# 10-10.net
KiCad netlist of a schematic drawn in EasyEDA Pro
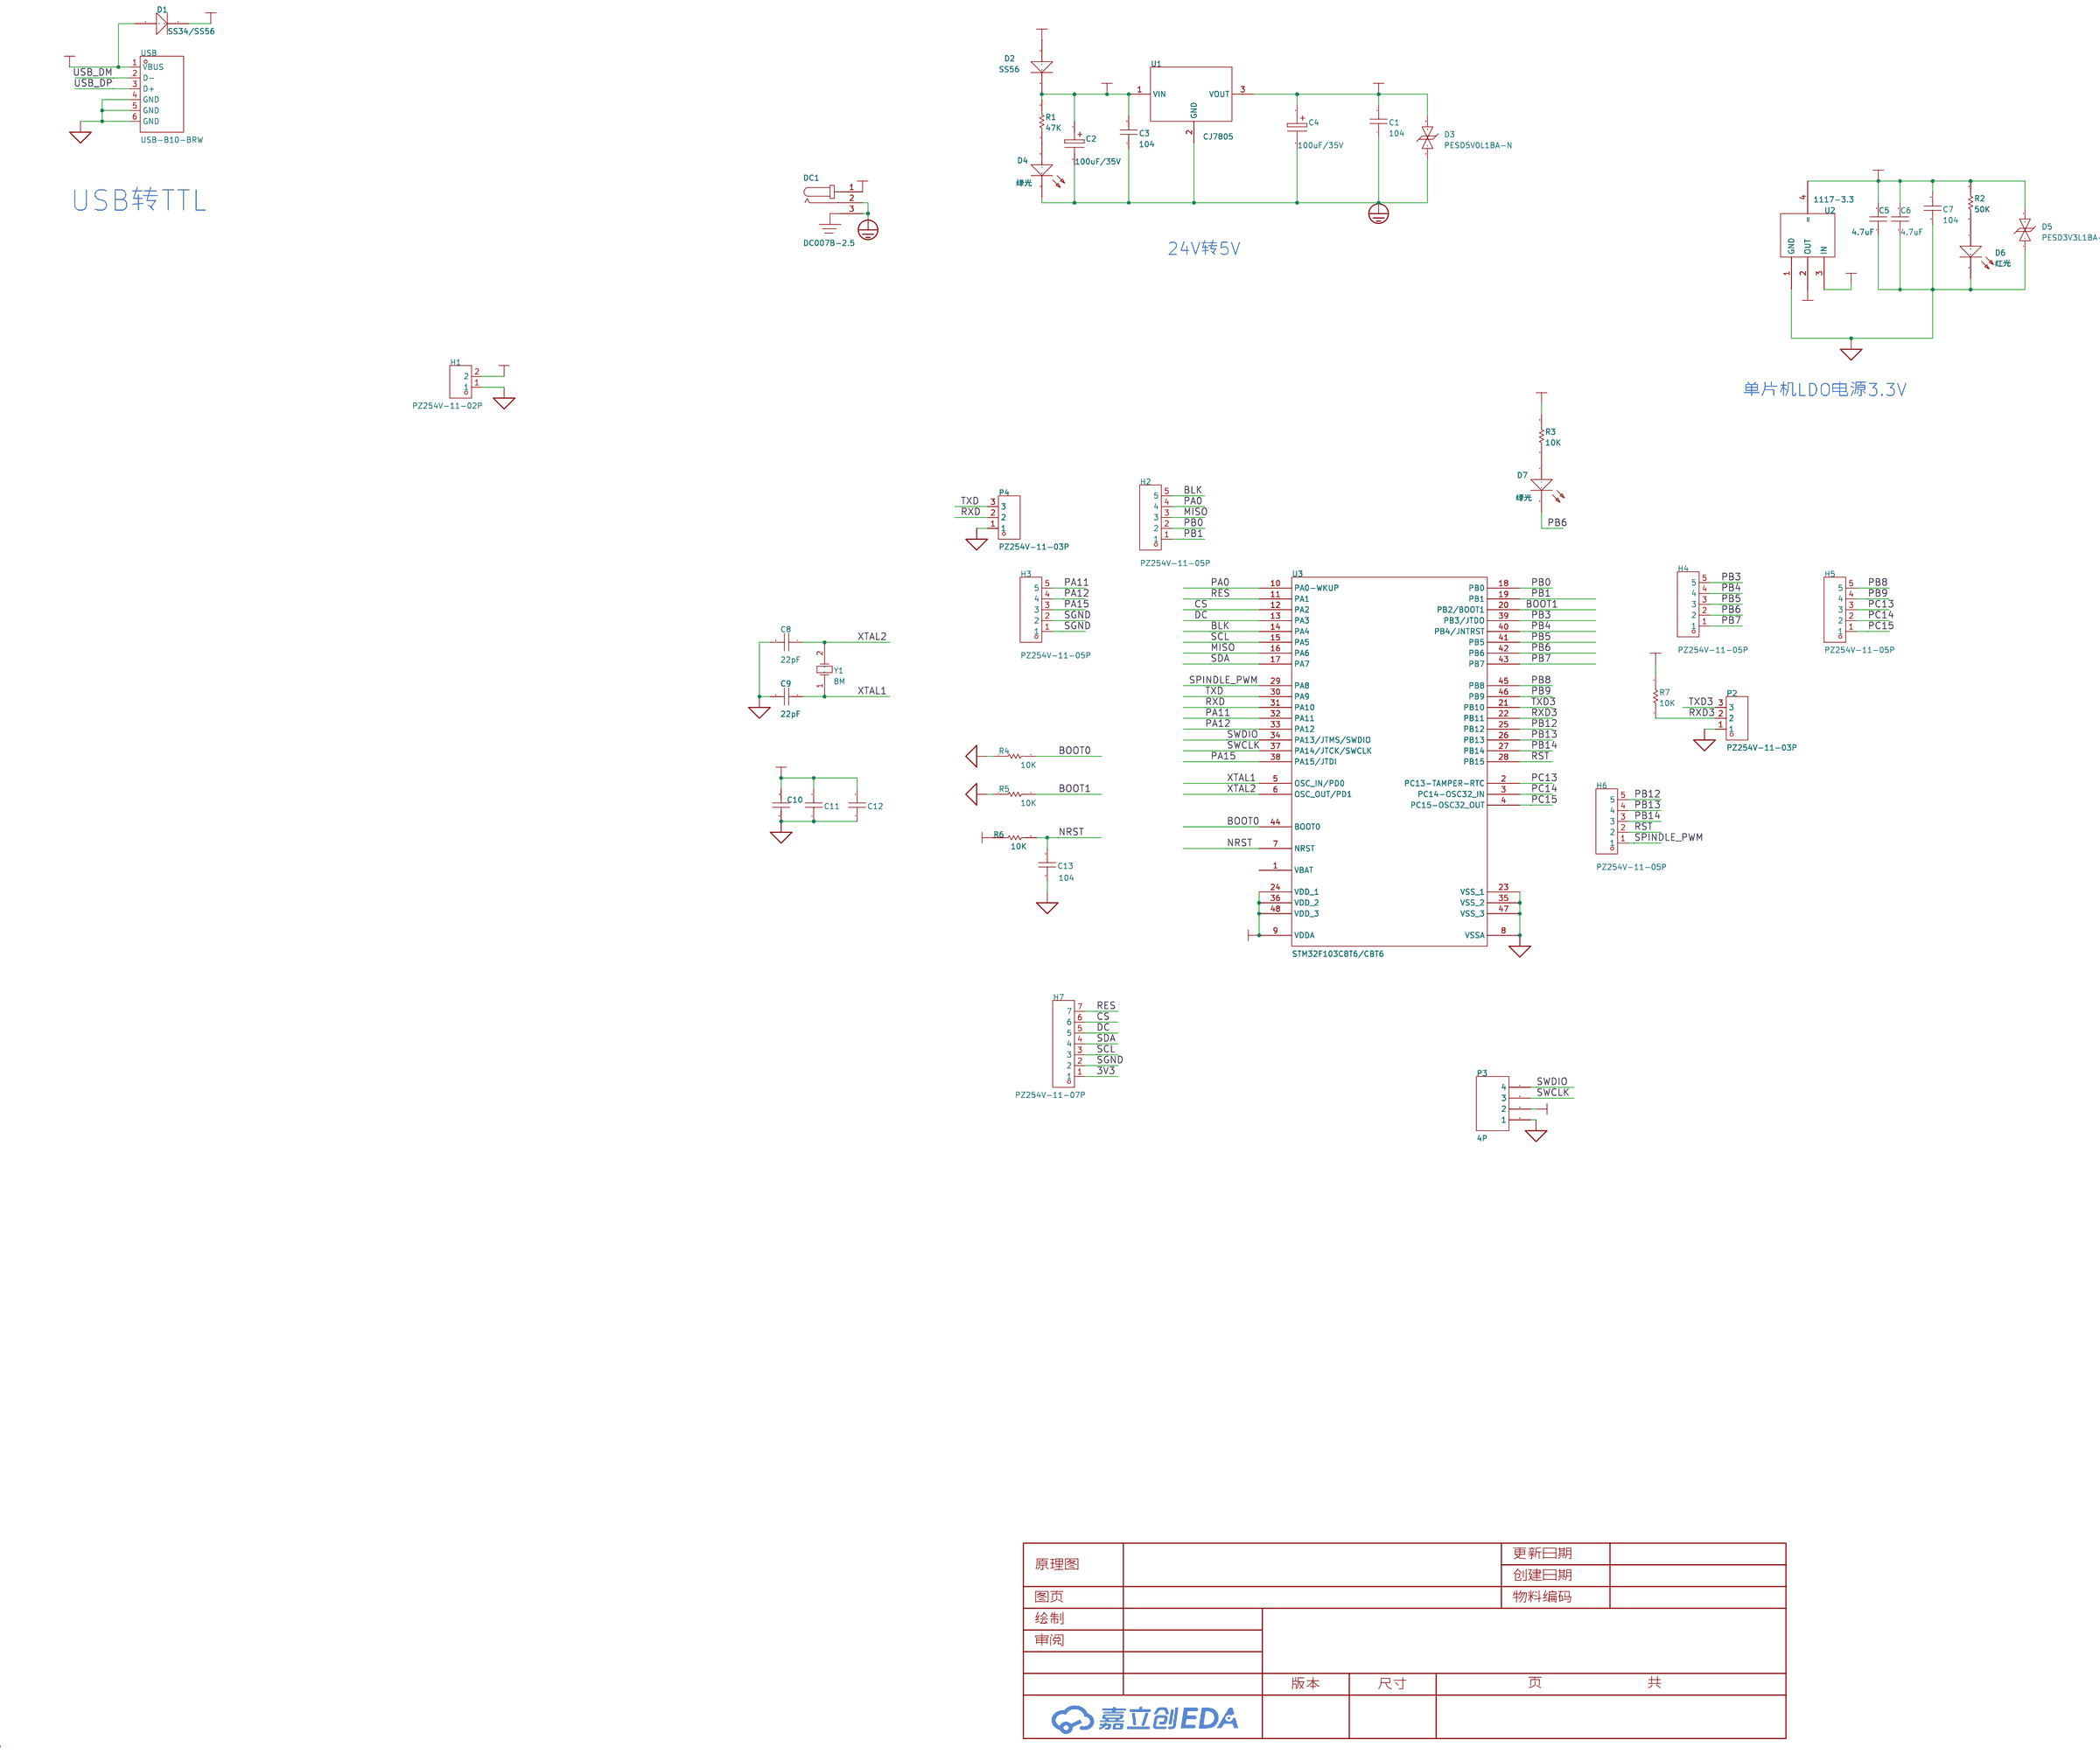
[diagram p0: 主控MCU]
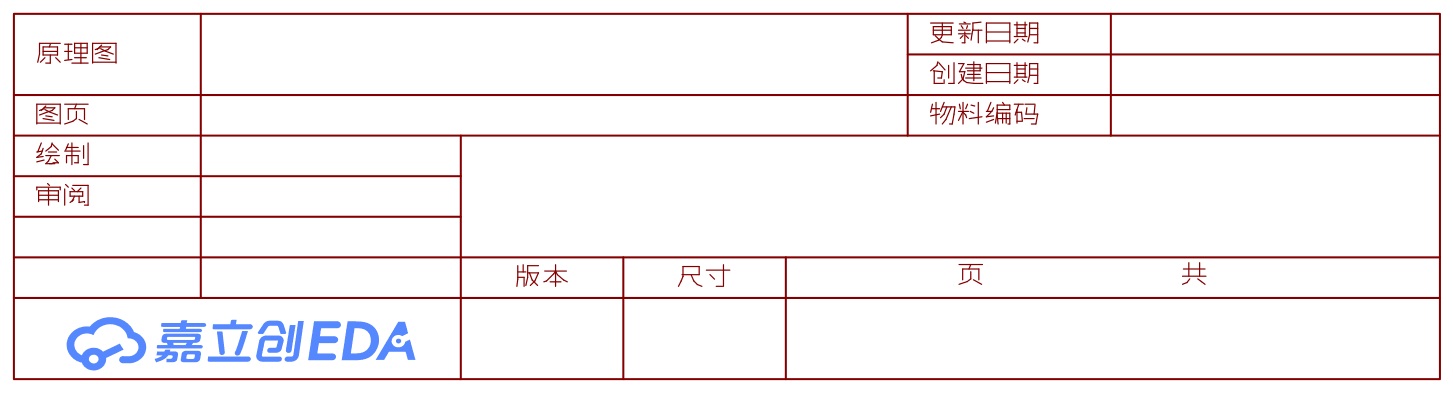
[diagram p1: 电源及控制]

(export (version "E")
  (design (tool "Eeschema 10.0.6"))
  (components
    (comp (ref "C1")
      (value "104")
      (footprint "easyedapro:0603C")
      (description "Capacitor (Semiconductor SIM Model)")
      (libsource (lib "easyedapro") (part "Cap Semi"))
    )
    (comp (ref "C2")
      (value "100uF/35V")
      (footprint "easyedapro:0603C")
      (libsource (lib "easyedapro") (part "ELECTRO1"))
    )
    (comp (ref "C3")
      (value "104")
      (footprint "easyedapro:0603C")
      (description "Capacitor (Semiconductor SIM Model)")
      (libsource (lib "easyedapro") (part "Cap Semi"))
    )
    (comp (ref "C4")
      (value "100uF/35V")
      (footprint "easyedapro:0603C")
      (libsource (lib "easyedapro") (part "ELECTRO1"))
    )
    (comp (ref "C5") (value "4.7uF") (libsource (lib "") (part "CAP_1")))
    (comp (ref "C6") (value "4.7uF") (libsource (lib "") (part "CAP_1")))
    (comp (ref "C7")
      (value "104")
      (footprint "easyedapro:0603C")
      (description "Capacitor (Semiconductor SIM Model)")
      (libsource (lib "easyedapro") (part "Cap Semi"))
    )
    (comp (ref "C8")
      (value "100pF")
      (footprint "easyedapro:0603C")
      (description "Capacitor (Semiconductor SIM Model)")
      (libsource (lib "easyedapro") (part "Cap Semi"))
    )
    (comp (ref "C9")
      (value "100pF")
      (footprint "easyedapro:0603C")
      (description "Capacitor (Semiconductor SIM Model)")
      (libsource (lib "easyedapro") (part "Cap Semi"))
    )
    (comp (ref "C10")
      (value "104")
      (footprint "easyedapro:电解电容贴片6X6")
      (libsource (lib "easyedapro") (part "CAP"))
    )
    (comp (ref "C11")
      (value "104")
      (footprint "easyedapro:电解电容贴片6X6")
      (libsource (lib "easyedapro") (part "CAP"))
    )
    (comp (ref "C12")
      (value "104")
      (footprint "easyedapro:电解电容贴片6X6")
      (libsource (lib "easyedapro") (part "CAP"))
    )
    (comp (ref "C13")
      (value "104")
      (footprint "easyedapro:0603C")
      (description "Capacitor (Semiconductor SIM Model)")
      (libsource (lib "easyedapro") (part "Cap Semi"))
    )
    (comp (ref "D1")
      (value "SS34/SS56")
      (footprint "easyedapro:SMA")
      (libsource (lib "easyedapro") (part "1N4148"))
    )
    (comp (ref "D2")
      (value "SS56")
      (footprint "easyedapro:SMA")
      (libsource (lib "easyedapro") (part "1N4148"))
    )
    (comp (ref "D3")
      (value "PESD5V0L1BA-N")
      (footprint "easyedapro:SOD-523_L1.2-W0.8-LS1.6-BI")
      (description "极性:Bidirectional;反向关断电压（典型值）:5V (Max);击穿电压（最小值）:6V;箝位电压:15V;峰值脉冲电流（10/1000us）:5A (8/20us);")
      (fields (field (name "Manufacturer") "BORN伯恩半导体"))
      (libsource (lib "easyedapro") (part "PESD5V0S1BBN"))
    )
    (comp (ref "D4")
      (value "绿光")
      (footprint "easyedapro:0603LED")
      (libsource (lib "easyedapro") (part "LED"))
    )
    (comp (ref "D5")
      (value "PESD3V3L1BA-N")
      (footprint "easyedapro:SOD-523_L1.2-W0.8-LS1.6-BI")
      (description "极性:Bidirectional;反向关断电压（典型值）:5V (Max);击穿电压（最小值）:6V;箝位电压:15V;峰值脉冲电流（10/1000us）:5A (8/20us);")
      (fields (field (name "Manufacturer") "BORN伯恩半导体"))
      (libsource (lib "easyedapro") (part "PESD5V0S1BBN"))
    )
    (comp (ref "D6")
      (value "红光")
      (footprint "easyedapro:0603LED")
      (libsource (lib "easyedapro") (part "LED"))
    )
    (comp (ref "D7")
      (value "绿光")
      (footprint "easyedapro:0603LED")
      (libsource (lib "easyedapro") (part "LED"))
    )
    (comp (ref "DC1")
      (value "DC007B-2.5")
      (footprint "easyedapro:DC-IN-TH_HX-DC007B-2.5")
      (description "连接器类型:DC电源插座;安装方式:弯插;触点内径:2.5mm;触点外径:7.7mm;额定电流:5A;额定电压:20V;工作温度:-25°C~+70°C;")
      (fields (field (name "Manufacturer") "SHOU HAN(首韩)"))
      (libsource (lib "easyedapro") (part "DC007B-2.5"))
    )
    (comp (ref "H1")
      (value "PZ254V-11-02P")
      (footprint "easyedapro:HDR-TH_2P-P2.54-V-M")
      (fields (field (name "Manufacturer") "XFCN(兴飞)"))
      (libsource (lib "easyedapro") (part "PZ254V-11-02P"))
    )
    (comp (ref "H2")
      (value "PZ254V-11-05P")
      (footprint "easyedapro:HDR-TH_5P-P2.54-V-M")
      (fields (field (name "Manufacturer") "XFCN(兴飞)"))
      (libsource (lib "easyedapro") (part "PZ254V-11-05P"))
    )
    (comp (ref "H3")
      (value "PZ254V-11-05P")
      (footprint "easyedapro:HDR-TH_5P-P2.54-V-M")
      (fields (field (name "Manufacturer") "XFCN(兴飞)"))
      (libsource (lib "easyedapro") (part "PZ254V-11-05P"))
    )
    (comp (ref "H4")
      (value "PZ254V-11-05P")
      (footprint "easyedapro:HDR-TH_5P-P2.54-V-M")
      (fields (field (name "Manufacturer") "XFCN(兴飞)"))
      (libsource (lib "easyedapro") (part "PZ254V-11-05P"))
    )
    (comp (ref "H5")
      (value "PZ254V-11-05P")
      (footprint "easyedapro:HDR-TH_5P-P2.54-V-M")
      (fields (field (name "Manufacturer") "XFCN(兴飞)"))
      (libsource (lib "easyedapro") (part "PZ254V-11-05P"))
    )
    (comp (ref "H6")
      (value "PZ254V-11-05P")
      (footprint "easyedapro:HDR-TH_5P-P2.54-V-M")
      (fields (field (name "Manufacturer") "XFCN(兴飞)"))
      (libsource (lib "easyedapro") (part "PZ254V-11-05P"))
    )
    (comp (ref "H7")
      (value "PZ254V-11-07P")
      (footprint "easyedapro:HDR-TH_7P-P2.54-V-M")
      (fields (field (name "Manufacturer") "XFCN(兴飞)"))
      (libsource (lib "easyedapro") (part "PZ254V-11-07P"))
    )
    (comp (ref "P2")
      (value "PZ254V-11-03P")
      (footprint "easyedapro:HDR-TH_3P-P2.54-V-M")
      (fields (field (name "Manufacturer") "XFCN(兴飞)"))
      (libsource (lib "easyedapro") (part "PZ254V-11-03P_C2937625"))
    )
    (comp (ref "P3") (value "4P") (libsource (lib "easyedapro") (part "4P")))
    (comp (ref "P4")
      (value "PZ254V-11-03P")
      (footprint "easyedapro:HDR-TH_3P-P2.54-V-M")
      (fields (field (name "Manufacturer") "XFCN(兴飞)"))
      (libsource (lib "easyedapro") (part "PZ254V-11-03P_C2937625"))
    )
    (comp (ref "R1")
      (value "47K")
      (footprint "easyedapro:0603R")
      (description "Resistor")
      (libsource (lib "easyedapro") (part "RES"))
    )
    (comp (ref "R2")
      (value "50K")
      (footprint "easyedapro:0603R")
      (description "Resistor")
      (libsource (lib "easyedapro") (part "RES"))
    )
    (comp (ref "R3")
      (value "10K")
      (footprint "easyedapro:0603R")
      (description "Resistor")
      (libsource (lib "easyedapro") (part "RES"))
    )
    (comp (ref "R4")
      (value "10K")
      (footprint "easyedapro:0603R")
      (description "Resistor")
      (libsource (lib "easyedapro") (part "RES"))
    )
    (comp (ref "R5")
      (value "10K")
      (footprint "easyedapro:0603R")
      (description "Resistor")
      (libsource (lib "easyedapro") (part "RES"))
    )
    (comp (ref "R6")
      (value "10K")
      (footprint "easyedapro:0603R")
      (description "Resistor")
      (libsource (lib "easyedapro") (part "RES"))
    )
    (comp (ref "R7")
      (value "10K")
      (footprint "easyedapro:0603R")
      (description "Resistor")
      (libsource (lib "easyedapro") (part "RES"))
    )
    (comp (ref "U1")
      (value "CJ7805")
      (footprint "easyedapro:TO-263-2")
      (libsource (lib "easyedapro") (part "7805"))
    )
    (comp (ref "U2")
      (value "1117-3.3")
      (footprint "easyedapro:SOT-223")
      (libsource (lib "easyedapro") (part "LM1117"))
    )
    (comp (ref "U3")
      (value "STM32F103C8T6/CBT6")
      (footprint "easyedapro:LQFP48")
      (description "STM32 ARM-based 32-bit MCU with 32 Kbytes Flash, 48-pin LQFP, Industrial Temperature")
      (libsource (lib "easyedapro") (part "STM32F103C6T6"))
    )
    (comp (ref "USB")
      (value "USB-B10-BRW")
      (footprint "easyedapro:USB-B-TH_USB-B10-BRW")
      (fields (field (name "Manufacturer") "XUNPU(讯普)"))
      (libsource (lib "easyedapro") (part "USB-B10-BRW"))
    )
    (comp (ref "Y1")
      (value "8M")
      (footprint "easyedapro:晶振贴片49SSMD")
      (description "Crystal Oscillator")
      (libsource (lib "easyedapro") (part "XTAL"))
    )
  )
  (nets
    (net (code "1") (name "3V3") (class "Default")
      (node (ref "C10") (pin "2") (pinfunction "2_2") (pintype "unspecified"))
      (node (ref "C11") (pin "2") (pinfunction "2_2") (pintype "unspecified"))
      (node (ref "C12") (pin "2") (pinfunction "2_2") (pintype "unspecified"))
      (node (ref "C5") (pin "2") (pinfunction "2_2") (pintype "input"))
      (node (ref "C6") (pin "2") (pinfunction "2_2") (pintype "input"))
      (node (ref "C7") (pin "2") (pinfunction "2_2") (pintype "unspecified"))
      (node (ref "D5") (pin "2") (pinfunction "2_2") (pintype "input"))
      (node (ref "H7") (pin "1") (pinfunction "1_1") (pintype "unspecified"))
      (node (ref "P3") (pin "2") (pinfunction "2_2") (pintype "input"))
      (node (ref "R2") (pin "1") (pinfunction "1_1") (pintype "unspecified"))
      (node (ref "R3") (pin "2") (pinfunction "2_2") (pintype "unspecified"))
      (node (ref "R6") (pin "1") (pinfunction "1_1") (pintype "unspecified"))
      (node (ref "R7") (pin "2") (pinfunction "2_2") (pintype "unspecified"))
      (node (ref "U2") (pin "2") (pinfunction "OUT_2") (pintype "unspecified"))
      (node (ref "U2") (pin "4") (pinfunction "=_4") (pintype "unspecified"))
      (node (ref "U3") (pin "24") (pinfunction "VDD_1_24") (pintype "unspecified"))
      (node (ref "U3") (pin "36") (pinfunction "VDD_2_36") (pintype "unspecified"))
      (node (ref "U3") (pin "48") (pinfunction "VDD_3_48") (pintype "unspecified"))
      (node (ref "U3") (pin "9") (pinfunction "VDDA_9") (pintype "unspecified"))
    )
    (net (code "2") (name "5V_VCC") (class "Default")
      (node (ref "C1") (pin "2") (pinfunction "2_2") (pintype "unspecified"))
      (node (ref "C4") (pin "1") (pintype "unspecified"))
      (node (ref "D1") (pin "2") (pinfunction "2_2") (pintype "unspecified"))
      (node (ref "D3") (pin "2") (pinfunction "2_2") (pintype "input"))
      (node (ref "H1") (pin "2") (pinfunction "2_2") (pintype "unspecified"))
      (node (ref "U1") (pin "3") (pinfunction "VOUT_3") (pintype "unspecified"))
      (node (ref "U2") (pin "3") (pinfunction "IN_3") (pintype "unspecified"))
    )
    (net (code "3") (name "24V") (class "Default")
      (node (ref "D2") (pin "1") (pinfunction "1_1") (pintype "unspecified"))
      (node (ref "DC1") (pin "1") (pinfunction "1_1") (pintype "unspecified"))
    )
    (net (code "4") (name "BLK") (class "Default")
      (node (ref "H2") (pin "5") (pinfunction "5_5") (pintype "input"))
      (node (ref "U3") (pin "14") (pinfunction "PA4_14") (pintype "bidirectional"))
    )
    (net (code "5") (name "BOOT0") (class "Default")
      (node (ref "R4") (pin "2") (pinfunction "2_2") (pintype "unspecified"))
      (node (ref "U3") (pin "44") (pinfunction "BOOT0_44") (pintype "input"))
    )
    (net (code "6") (name "BOOT1") (class "Default")
      (node (ref "R5") (pin "2") (pinfunction "2_2") (pintype "unspecified"))
      (node (ref "U3") (pin "20") (pinfunction "PB2/BOOT1_20") (pintype "bidirectional"))
    )
    (net (code "7") (name "CS") (class "Default")
      (node (ref "H7") (pin "6") (pinfunction "6_6") (pintype "unspecified"))
      (node (ref "U3") (pin "12") (pinfunction "PA2_12") (pintype "bidirectional"))
    )
    (net (code "8") (name "DC") (class "Default")
      (node (ref "H7") (pin "5") (pinfunction "5_5") (pintype "unspecified"))
      (node (ref "U3") (pin "13") (pinfunction "PA3_13") (pintype "bidirectional"))
    )
    (net (code "9") (name "MISO") (class "Default")
      (node (ref "H2") (pin "3") (pinfunction "3_3") (pintype "input"))
      (node (ref "U3") (pin "16") (pinfunction "PA6_16") (pintype "bidirectional"))
    )
    (net (code "10") (name "NRST") (class "Default")
      (node (ref "C13") (pin "2") (pinfunction "2_2") (pintype "unspecified"))
      (node (ref "R6") (pin "2") (pinfunction "2_2") (pintype "unspecified"))
      (node (ref "U3") (pin "7") (pinfunction "NRST_7") (pintype "bidirectional"))
    )
    (net (code "11") (name "Net-(D4-Pad1)") (class "Default")
      (node (ref "D4") (pin "1") (pinfunction "1_1") (pintype "unspecified"))
      (node (ref "R1") (pin "1") (pinfunction "1_1") (pintype "unspecified"))
    )
    (net (code "12") (name "Net-(D6-Pad1)") (class "Default")
      (node (ref "D6") (pin "1") (pinfunction "1_1") (pintype "unspecified"))
      (node (ref "R2") (pin "2") (pinfunction "2_2") (pintype "unspecified"))
    )
    (net (code "13") (name "Net-(D7-Pad1)") (class "Default")
      (node (ref "D7") (pin "1") (pinfunction "1_1") (pintype "unspecified"))
      (node (ref "R3") (pin "1") (pinfunction "1_1") (pintype "unspecified"))
    )
    (net (code "14") (name "PA0") (class "Default")
      (node (ref "H2") (pin "4") (pinfunction "4_4") (pintype "input"))
      (node (ref "U3") (pin "10") (pinfunction "PA0-WKUP_10") (pintype "bidirectional"))
    )
    (net (code "15") (name "PA11") (class "Default")
      (node (ref "H3") (pin "5") (pinfunction "5_5") (pintype "input"))
      (node (ref "U3") (pin "32") (pinfunction "PA11_32") (pintype "bidirectional"))
    )
    (net (code "16") (name "PA12") (class "Default")
      (node (ref "H3") (pin "4") (pinfunction "4_4") (pintype "input"))
      (node (ref "U3") (pin "33") (pinfunction "PA12_33") (pintype "bidirectional"))
    )
    (net (code "17") (name "PA15") (class "Default")
      (node (ref "H3") (pin "3") (pinfunction "3_3") (pintype "input"))
      (node (ref "U3") (pin "38") (pinfunction "PA15/JTDI_38") (pintype "bidirectional"))
    )
    (net (code "18") (name "PB0") (class "Default")
      (node (ref "H2") (pin "2") (pinfunction "2_2") (pintype "input"))
      (node (ref "U3") (pin "18") (pinfunction "PB0_18") (pintype "bidirectional"))
    )
    (net (code "19") (name "PB1") (class "Default")
      (node (ref "H2") (pin "1") (pinfunction "1_1") (pintype "input"))
      (node (ref "U3") (pin "19") (pinfunction "PB1_19") (pintype "bidirectional"))
    )
    (net (code "20") (name "PB3") (class "Default")
      (node (ref "H4") (pin "5") (pinfunction "5_5") (pintype "input"))
      (node (ref "U3") (pin "39") (pinfunction "PB3/JTDO_39") (pintype "bidirectional"))
    )
    (net (code "21") (name "PB4") (class "Default")
      (node (ref "H4") (pin "4") (pinfunction "4_4") (pintype "input"))
      (node (ref "U3") (pin "40") (pinfunction "PB4/JNTRST_40") (pintype "bidirectional"))
    )
    (net (code "22") (name "PB5") (class "Default")
      (node (ref "H4") (pin "3") (pinfunction "3_3") (pintype "input"))
      (node (ref "U3") (pin "41") (pinfunction "PB5_41") (pintype "bidirectional"))
    )
    (net (code "23") (name "PB6") (class "Default")
      (node (ref "D7") (pin "2") (pinfunction "2_2") (pintype "unspecified"))
      (node (ref "H4") (pin "2") (pinfunction "2_2") (pintype "input"))
      (node (ref "U3") (pin "42") (pinfunction "PB6_42") (pintype "bidirectional"))
    )
    (net (code "24") (name "PB7") (class "Default")
      (node (ref "H4") (pin "1") (pinfunction "1_1") (pintype "input"))
      (node (ref "U3") (pin "43") (pinfunction "PB7_43") (pintype "bidirectional"))
    )
    (net (code "25") (name "PB8") (class "Default")
      (node (ref "H5") (pin "5") (pinfunction "5_5") (pintype "input"))
      (node (ref "U3") (pin "45") (pinfunction "PB8_45") (pintype "bidirectional"))
    )
    (net (code "26") (name "PB9") (class "Default")
      (node (ref "H5") (pin "4") (pinfunction "4_4") (pintype "input"))
      (node (ref "U3") (pin "46") (pinfunction "PB9_46") (pintype "bidirectional"))
    )
    (net (code "27") (name "PB12") (class "Default")
      (node (ref "H6") (pin "5") (pinfunction "5_5") (pintype "input"))
      (node (ref "U3") (pin "25") (pinfunction "PB12_25") (pintype "bidirectional"))
    )
    (net (code "28") (name "PB13") (class "Default")
      (node (ref "H6") (pin "4") (pinfunction "4_4") (pintype "input"))
      (node (ref "U3") (pin "26") (pinfunction "PB13_26") (pintype "bidirectional"))
    )
    (net (code "29") (name "PB14") (class "Default")
      (node (ref "H6") (pin "3") (pinfunction "3_3") (pintype "input"))
      (node (ref "U3") (pin "27") (pinfunction "PB14_27") (pintype "bidirectional"))
    )
    (net (code "30") (name "PC13") (class "Default")
      (node (ref "H5") (pin "3") (pinfunction "3_3") (pintype "input"))
      (node (ref "U3") (pin "2") (pinfunction "PC13-TAMPER-RTC_2") (pintype "bidirectional"))
    )
    (net (code "31") (name "PC14") (class "Default")
      (node (ref "H5") (pin "2") (pinfunction "2_2") (pintype "input"))
      (node (ref "U3") (pin "3") (pinfunction "PC14-OSC32_IN_3") (pintype "bidirectional"))
    )
    (net (code "32") (name "PC15") (class "Default")
      (node (ref "H5") (pin "1") (pinfunction "1_1") (pintype "input"))
      (node (ref "U3") (pin "4") (pinfunction "PC15-OSC32_OUT_4") (pintype "bidirectional"))
    )
    (net (code "33") (name "RES") (class "Default")
      (node (ref "H7") (pin "7") (pinfunction "7_7") (pintype "unspecified"))
      (node (ref "U3") (pin "11") (pinfunction "PA1_11") (pintype "bidirectional"))
    )
    (net (code "34") (name "RST") (class "Default")
      (node (ref "H6") (pin "2") (pinfunction "2_2") (pintype "input"))
      (node (ref "U3") (pin "28") (pinfunction "PB15_28") (pintype "bidirectional"))
    )
    (net (code "35") (name "RXD") (class "Default")
      (node (ref "P4") (pin "2") (pinfunction "2_2") (pintype "unspecified"))
      (node (ref "U3") (pin "31") (pinfunction "PA10_31") (pintype "bidirectional"))
    )
    (net (code "36") (name "RXD3") (class "Default")
      (node (ref "P2") (pin "2") (pinfunction "2_2") (pintype "unspecified"))
      (node (ref "R7") (pin "1") (pinfunction "1_1") (pintype "unspecified"))
      (node (ref "U3") (pin "22") (pinfunction "PB11_22") (pintype "bidirectional"))
    )
    (net (code "37") (name "SCL") (class "Default")
      (node (ref "H7") (pin "3") (pinfunction "3_3") (pintype "unspecified"))
      (node (ref "U3") (pin "15") (pinfunction "PA5_15") (pintype "bidirectional"))
    )
    (net (code "38") (name "SDA") (class "Default")
      (node (ref "H7") (pin "4") (pinfunction "4_4") (pintype "unspecified"))
      (node (ref "U3") (pin "17") (pinfunction "PA7_17") (pintype "bidirectional"))
    )
    (net (code "39") (name "SGND") (class "Default")
      (node (ref "C1") (pin "1") (pinfunction "1_1") (pintype "unspecified"))
      (node (ref "C10") (pin "1") (pinfunction "1_1") (pintype "unspecified"))
      (node (ref "C11") (pin "1") (pinfunction "1_1") (pintype "unspecified"))
      (node (ref "C12") (pin "1") (pinfunction "1_1") (pintype "unspecified"))
      (node (ref "C13") (pin "1") (pinfunction "1_1") (pintype "unspecified"))
      (node (ref "C2") (pin "2") (pintype "unspecified"))
      (node (ref "C3") (pin "1") (pinfunction "1_1") (pintype "unspecified"))
      (node (ref "C4") (pin "2") (pintype "unspecified"))
      (node (ref "C5") (pin "1") (pinfunction "1_1") (pintype "input"))
      (node (ref "C6") (pin "1") (pinfunction "1_1") (pintype "input"))
      (node (ref "C7") (pin "1") (pinfunction "1_1") (pintype "unspecified"))
      (node (ref "C8") (pin "2") (pinfunction "2_2") (pintype "unspecified"))
      (node (ref "C9") (pin "2") (pinfunction "2_2") (pintype "unspecified"))
      (node (ref "D3") (pin "1") (pinfunction "1_1") (pintype "input"))
      (node (ref "D4") (pin "2") (pinfunction "2_2") (pintype "unspecified"))
      (node (ref "D5") (pin "1") (pinfunction "1_1") (pintype "input"))
      (node (ref "D6") (pin "2") (pinfunction "2_2") (pintype "unspecified"))
      (node (ref "DC1") (pin "2") (pinfunction "2_2") (pintype "unspecified"))
      (node (ref "DC1") (pin "3") (pinfunction "3_3") (pintype "unspecified"))
      (node (ref "H1") (pin "1") (pinfunction "1_1") (pintype "unspecified"))
      (node (ref "H3") (pin "1") (pinfunction "1_1") (pintype "input"))
      (node (ref "H3") (pin "2") (pinfunction "2_2") (pintype "input"))
      (node (ref "H7") (pin "2") (pinfunction "2_2") (pintype "unspecified"))
      (node (ref "P2") (pin "1") (pinfunction "1_1") (pintype "unspecified"))
      (node (ref "P3") (pin "1") (pinfunction "1_1") (pintype "input"))
      (node (ref "P4") (pin "1") (pinfunction "1_1") (pintype "unspecified"))
      (node (ref "R4") (pin "1") (pinfunction "1_1") (pintype "unspecified"))
      (node (ref "R5") (pin "1") (pinfunction "1_1") (pintype "unspecified"))
      (node (ref "U1") (pin "2") (pinfunction "GND_2") (pintype "unspecified"))
      (node (ref "U2") (pin "1") (pinfunction "GND_1") (pintype "unspecified"))
      (node (ref "U3") (pin "23") (pinfunction "VSS_1_23") (pintype "unspecified"))
      (node (ref "U3") (pin "35") (pinfunction "VSS_2_35") (pintype "unspecified"))
      (node (ref "U3") (pin "47") (pinfunction "VSS_3_47") (pintype "unspecified"))
      (node (ref "U3") (pin "8") (pinfunction "VSSA_8") (pintype "unspecified"))
      (node (ref "USB") (pin "4") (pinfunction "GND_4") (pintype "unspecified"))
      (node (ref "USB") (pin "5") (pinfunction "GND_5") (pintype "unspecified"))
      (node (ref "USB") (pin "6") (pinfunction "GND_6") (pintype "unspecified"))
    )
    (net (code "40") (name "SPINDLE_PWM") (class "Default")
      (node (ref "H6") (pin "1") (pinfunction "1_1") (pintype "input"))
      (node (ref "U3") (pin "29") (pinfunction "PA8_29") (pintype "bidirectional"))
    )
    (net (code "41") (name "SWCLK") (class "Default")
      (node (ref "P3") (pin "3") (pinfunction "3_3") (pintype "input"))
      (node (ref "U3") (pin "37") (pinfunction "PA14/JTCK/SWCLK_37") (pintype "bidirectional"))
    )
    (net (code "42") (name "SWDIO") (class "Default")
      (node (ref "P3") (pin "4") (pinfunction "4_4") (pintype "input"))
      (node (ref "U3") (pin "34") (pinfunction "PA13/JTMS/SWDIO_34") (pintype "bidirectional"))
    )
    (net (code "43") (name "TXD") (class "Default")
      (node (ref "P4") (pin "3") (pinfunction "3_3") (pintype "unspecified"))
      (node (ref "U3") (pin "30") (pinfunction "PA9_30") (pintype "bidirectional"))
    )
    (net (code "44") (name "TXD3") (class "Default")
      (node (ref "P2") (pin "3") (pinfunction "3_3") (pintype "unspecified"))
      (node (ref "U3") (pin "21") (pinfunction "PB10_21") (pintype "bidirectional"))
    )
    (net (code "45") (name "USB_DM") (class "Default")
      (node (ref "USB") (pin "2") (pinfunction "D-_2") (pintype "unspecified"))
    )
    (net (code "46") (name "USB_DP") (class "Default")
      (node (ref "USB") (pin "3") (pinfunction "D+_3") (pintype "unspecified"))
    )
    (net (code "47") (name "VIN_24V") (class "Default")
      (node (ref "C2") (pin "1") (pintype "unspecified"))
      (node (ref "C3") (pin "2") (pinfunction "2_2") (pintype "unspecified"))
      (node (ref "D2") (pin "2") (pinfunction "2_2") (pintype "unspecified"))
      (node (ref "R1") (pin "2") (pinfunction "2_2") (pintype "unspecified"))
      (node (ref "U1") (pin "1") (pinfunction "VIN_1") (pintype "unspecified"))
    )
    (net (code "48") (name "VUSB") (class "Default")
      (node (ref "D1") (pin "1") (pinfunction "1_1") (pintype "unspecified"))
      (node (ref "USB") (pin "1") (pinfunction "VBUS_1") (pintype "unspecified"))
    )
    (net (code "49") (name "XTAL1") (class "Default")
      (node (ref "C9") (pin "1") (pinfunction "1_1") (pintype "unspecified"))
      (node (ref "U3") (pin "5") (pinfunction "OSC_IN/PD0_5") (pintype "input"))
      (node (ref "Y1") (pin "1") (pinfunction "OSC1_1") (pintype "unspecified"))
    )
    (net (code "50") (name "XTAL2") (class "Default")
      (node (ref "C8") (pin "1") (pinfunction "1_1") (pintype "unspecified"))
      (node (ref "U3") (pin "6") (pinfunction "OSC_OUT/PD1_6") (pintype "output"))
      (node (ref "Y1") (pin "2") (pinfunction "OSC2_2") (pintype "unspecified"))
    )
    (net (code "51") (name "unconnected-(U3-VBAT-Pad1)") (class "Default")
      (node (ref "U3") (pin "1") (pinfunction "VBAT_1") (pintype "unspecified"))
    )
  )
)
